# ArduinoRgbFanController.net
KiCad netlist of a schematic drawn in EAGLE
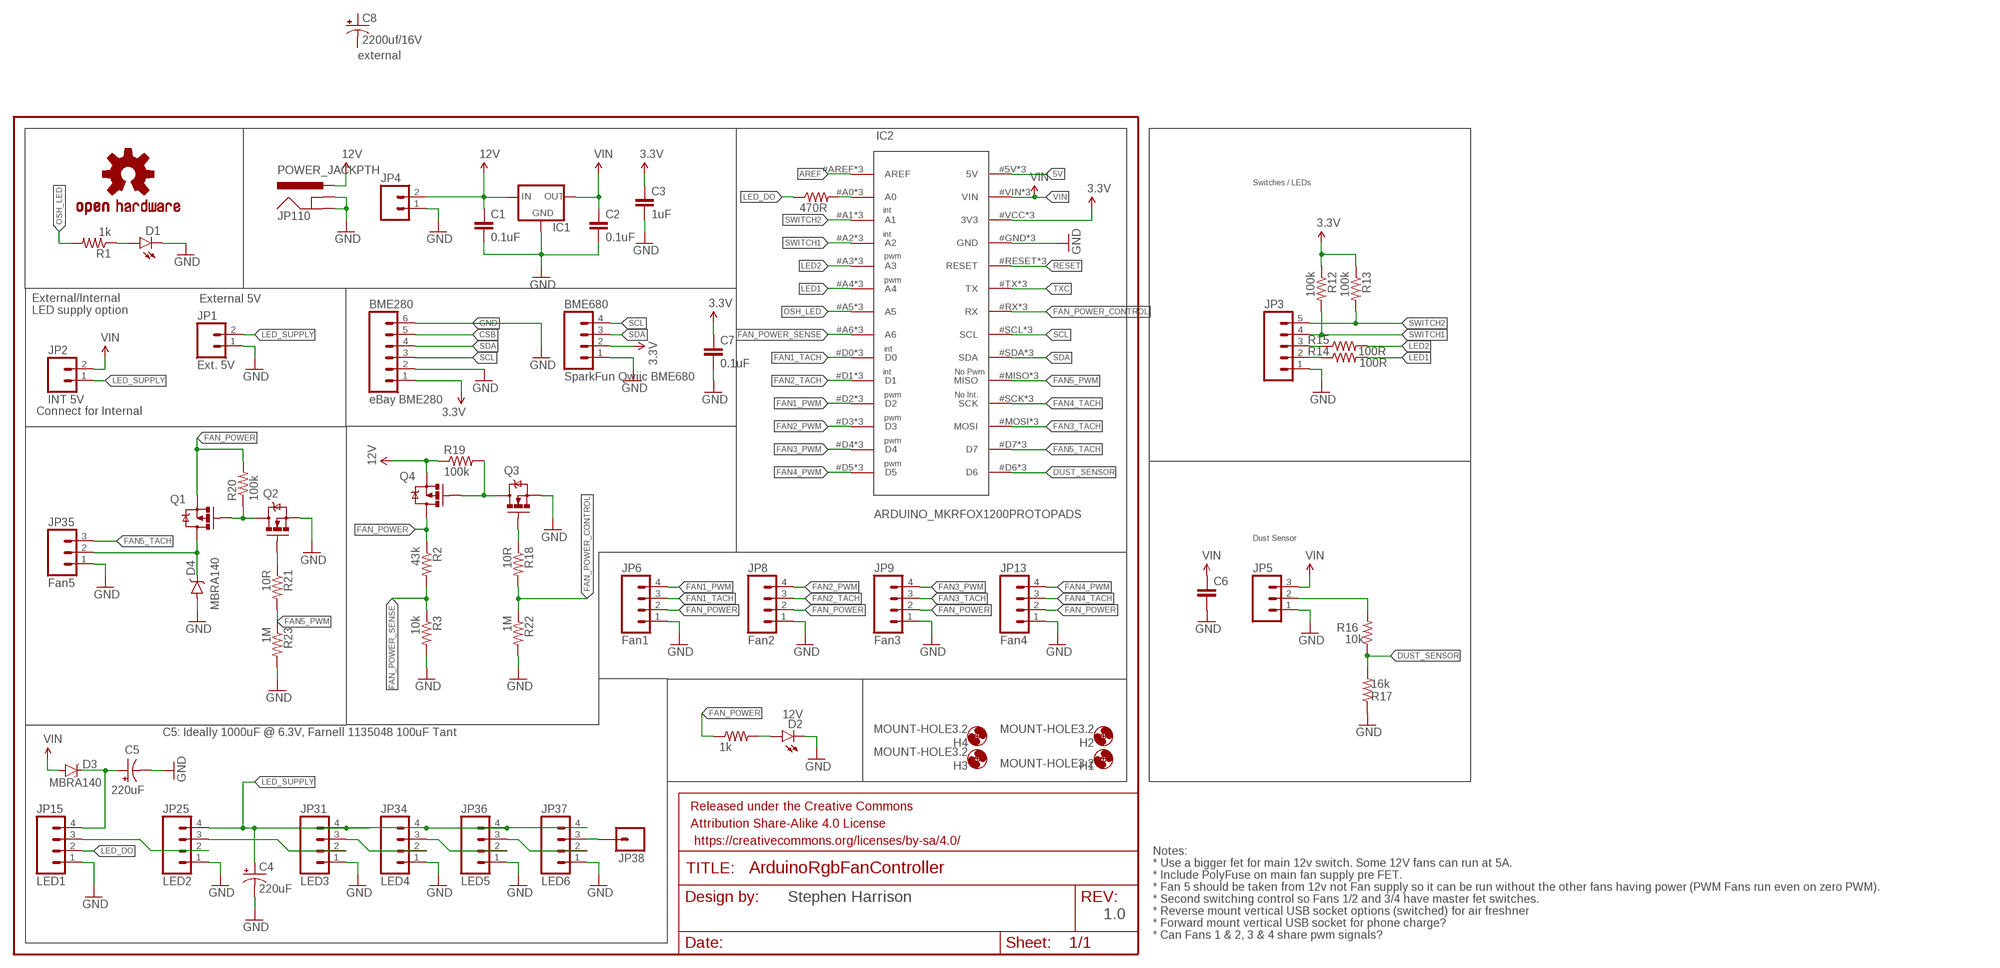
[diagram p0: schematic, sheet 1]

(export (version "E")
  (design (tool "Eeschema 10.0.6"))
  (components
    (comp (ref "BME280")
      (value "eBay BME280")
      (footprint "eagle-import:1X06")
      (libsource (lib "eagle-import") (part "M06SILK_FEMALE_PTH"))
    )
    (comp (ref "BME680")
      (value "SparkFun Qwiic BME680")
      (footprint "eagle-import:1X04")
      (libsource (lib "eagle-import") (part "M04PTH"))
    )
    (comp (ref "C1")
      (value "0.1uF")
      (footprint "eagle-import:0805-CAP")
      (libsource (lib "eagle-import") (part "1UF-25V-10%(0805){dblquote}"))
    )
    (comp (ref "C2")
      (value "0.1uF")
      (footprint "eagle-import:0805-CAP")
      (libsource (lib "eagle-import") (part "1UF-25V-10%(0805){dblquote}"))
    )
    (comp (ref "C3")
      (value "1uF")
      (footprint "eagle-import:0805-CAP")
      (libsource (lib "eagle-import") (part "1UF-25V-10%(0805){dblquote}"))
    )
    (comp (ref "C4")
      (value "220uF")
      (footprint "eagle-import:EIA3528")
      (libsource (lib "eagle-import") (part "47UF-10V-10%(TANT)"))
    )
    (comp (ref "C5")
      (value "220uF")
      (footprint "eagle-import:EIA3528")
      (libsource (lib "eagle-import") (part "47UF-10V-10%(TANT)"))
    )
    (comp (ref "C6")
      (value "1UF-25V-10%(0805)\"")
      (footprint "eagle-import:0805-CAP")
      (libsource (lib "eagle-import") (part "1UF-25V-10%(0805){dblquote}"))
    )
    (comp (ref "C7")
      (value "0.1uF")
      (footprint "eagle-import:0805-CAP")
      (libsource (lib "eagle-import") (part "1UF-25V-10%(0805){dblquote}"))
    )
    (comp (ref "C8")
      (value "2200uf/16V")
      (footprint "eagle-import:CPOL-RADIAL-1000UF-25V-KIT")
      (libsource (lib "eagle-import") (part "1000UF-25V(PTH)KIT"))
    )
    (comp (ref "D1")
      (value "LED1206-BOTTOM")
      (footprint "eagle-import:LED-1206-BOTTOM")
      (libsource (lib "eagle-import") (part "LED1206-BOTTOM"))
    )
    (comp (ref "D2")
      (value "12V")
      (footprint "eagle-import:LED-1206")
      (libsource (lib "eagle-import") (part "LED-RED1206"))
    )
    (comp (ref "D3")
      (value "MBRA140")
      (footprint "eagle-import:SMA-DIODE")
      (libsource (lib "eagle-import") (part "DIODE-SCHOTTKY-MBRA140"))
    )
    (comp (ref "D4")
      (value "MBRA140")
      (footprint "eagle-import:SMA-DIODE")
      (libsource (lib "eagle-import") (part "DIODE-SCHOTTKY-MBRA140"))
    )
    (comp (ref "FRAME1")
      (value "FRAME-LETTER")
      (footprint "eagle-import:CREATIVE_COMMONS")
      (libsource (lib "eagle-import") (part "FRAME-LETTER"))
    )
    (comp (ref "H1")
      (value "MOUNT-HOLE3.2")
      (footprint "eagle-import:3,2")
      (libsource (lib "eagle-import") (part "MOUNT-HOLE3.2"))
    )
    (comp (ref "H2")
      (value "MOUNT-HOLE3.2")
      (footprint "eagle-import:3,2")
      (libsource (lib "eagle-import") (part "MOUNT-HOLE3.2"))
    )
    (comp (ref "H3")
      (value "MOUNT-HOLE3.2")
      (footprint "eagle-import:3,2")
      (libsource (lib "eagle-import") (part "MOUNT-HOLE3.2"))
    )
    (comp (ref "H4")
      (value "MOUNT-HOLE3.2")
      (footprint "eagle-import:3,2")
      (libsource (lib "eagle-import") (part "MOUNT-HOLE3.2"))
    )
    (comp (ref "IC1")
      (value "78XXS")
      (footprint "eagle-import:78XXS")
      (libsource (lib "eagle-import") (part "78XXS"))
    )
    (comp (ref "IC2")
      (value "ARDUINO_MKRFOX1200PROTOPADS")
      (footprint "eagle-import:ARDUINO_MKRFOX1200_PROTOPADS")
      (libsource (lib "eagle-import") (part "ARDUINO_MKRFOX1200PROTOPADS"))
    )
    (comp (ref "JP1")
      (value "Ext. 5V")
      (footprint "eagle-import:SCREWTERMINAL-3.5MM-2")
      (libsource (lib "eagle-import") (part "M023.5MM"))
    )
    (comp (ref "JP2")
      (value "INT 5V")
      (footprint "eagle-import:1X02")
      (libsource (lib "eagle-import") (part "M02PTH"))
    )
    (comp (ref "JP3")
      (value "M05PTH")
      (footprint "eagle-import:1X05")
      (libsource (lib "eagle-import") (part "M05PTH"))
    )
    (comp (ref "JP4")
      (value "M025MM")
      (footprint "eagle-import:SCREWTERMINAL-5MM-2")
      (libsource (lib "eagle-import") (part "M025MM"))
    )
    (comp (ref "JP5")
      (value "M03POLAR")
      (footprint "eagle-import:MOLEX-1X3")
      (libsource (lib "eagle-import") (part "M03POLAR"))
    )
    (comp (ref "JP6")
      (value "Fan1")
      (footprint "eagle-import:MOLEX-1X4")
      (libsource (lib "eagle-import") (part "M04POLAR"))
    )
    (comp (ref "JP8")
      (value "Fan2")
      (footprint "eagle-import:MOLEX-1X4")
      (libsource (lib "eagle-import") (part "M04POLAR"))
    )
    (comp (ref "JP9")
      (value "Fan3")
      (footprint "eagle-import:MOLEX-1X4")
      (libsource (lib "eagle-import") (part "M04POLAR"))
    )
    (comp (ref "JP13")
      (value "Fan4")
      (footprint "eagle-import:MOLEX-1X4")
      (libsource (lib "eagle-import") (part "M04POLAR"))
    )
    (comp (ref "JP15")
      (value "LED1")
      (footprint "eagle-import:1X04")
      (libsource (lib "eagle-import") (part "M04PTH"))
    )
    (comp (ref "JP25")
      (value "LED2")
      (footprint "eagle-import:1X04")
      (libsource (lib "eagle-import") (part "M04PTH"))
    )
    (comp (ref "JP31")
      (value "LED3")
      (footprint "eagle-import:1X04")
      (libsource (lib "eagle-import") (part "M04PTH"))
    )
    (comp (ref "JP34")
      (value "LED4")
      (footprint "eagle-import:1X04")
      (libsource (lib "eagle-import") (part "M04PTH"))
    )
    (comp (ref "JP35")
      (value "Fan5")
      (footprint "eagle-import:MOLEX-1X3")
      (libsource (lib "eagle-import") (part "M03POLAR"))
    )
    (comp (ref "JP36")
      (value "LED5")
      (footprint "eagle-import:1X04")
      (libsource (lib "eagle-import") (part "M04PTH"))
    )
    (comp (ref "JP37")
      (value "LED6")
      (footprint "eagle-import:1X04")
      (libsource (lib "eagle-import") (part "M04PTH"))
    )
    (comp (ref "JP38")
      (value "M01PTH")
      (footprint "eagle-import:1X01")
      (libsource (lib "eagle-import") (part "M01PTH"))
    )
    (comp (ref "JP110")
      (value "POWER_JACKPTH")
      (footprint "eagle-import:POWER_JACK_PTH")
      (libsource (lib "eagle-import") (part "POWER_JACKPTH"))
    )
    (comp (ref "LOGO3")
      (value "OSHW-LOGOM")
      (footprint "eagle-import:OSHW-LOGO-M")
      (libsource (lib "eagle-import") (part "OSHW-LOGOM"))
    )
    (comp (ref "Q1")
      (value "IRLML930")
      (footprint "eagle-import:SOT23-3")
      (libsource (lib "eagle-import") (part "MOSFET-PCHANNEL"))
    )
    (comp (ref "Q2")
      (value "2N7002")
      (footprint "eagle-import:SOT23-3")
      (libsource (lib "eagle-import") (part "MOSFET-NCHANNELAO3404A"))
    )
    (comp (ref "Q3")
      (value "2N7002")
      (footprint "eagle-import:SOT23-3")
      (libsource (lib "eagle-import") (part "MOSFET-NCHANNELAO3404A"))
    )
    (comp (ref "Q4")
      (value "IRLML930")
      (footprint "eagle-import:SOT23-3")
      (libsource (lib "eagle-import") (part "MOSFET-PCHANNEL"))
    )
    (comp (ref "R1")
      (value "1k")
      (footprint "eagle-import:0805")
      (libsource (lib "eagle-import") (part "RESISTOR0805-RES"))
    )
    (comp (ref "R2")
      (value "43k")
      (footprint "eagle-import:0805")
      (libsource (lib "eagle-import") (part "RESISTOR0805-RES"))
    )
    (comp (ref "R3")
      (value "10k")
      (footprint "eagle-import:0805")
      (libsource (lib "eagle-import") (part "RESISTOR0805-RES"))
    )
    (comp (ref "R11")
      (value "470R")
      (footprint "eagle-import:0805")
      (libsource (lib "eagle-import") (part "RESISTOR0805-RES"))
    )
    (comp (ref "R12")
      (value "100k")
      (footprint "eagle-import:0805")
      (libsource (lib "eagle-import") (part "RESISTOR0805-RES"))
    )
    (comp (ref "R13")
      (value "100k")
      (footprint "eagle-import:0805")
      (libsource (lib "eagle-import") (part "RESISTOR0805-RES"))
    )
    (comp (ref "R14")
      (value "100R")
      (footprint "eagle-import:0805")
      (libsource (lib "eagle-import") (part "RESISTOR0805-RES"))
    )
    (comp (ref "R15")
      (value "100R")
      (footprint "eagle-import:0805")
      (libsource (lib "eagle-import") (part "RESISTOR0805-RES"))
    )
    (comp (ref "R16")
      (value "10k")
      (footprint "eagle-import:0805")
      (libsource (lib "eagle-import") (part "RESISTOR0805-RES"))
    )
    (comp (ref "R17")
      (value "16k")
      (footprint "eagle-import:0805")
      (libsource (lib "eagle-import") (part "RESISTOR0805-RES"))
    )
    (comp (ref "R18")
      (value "10R")
      (footprint "eagle-import:0805")
      (libsource (lib "eagle-import") (part "RESISTOR0805-RES"))
    )
    (comp (ref "R19")
      (value "100k")
      (footprint "eagle-import:0805")
      (libsource (lib "eagle-import") (part "RESISTOR0805-RES"))
    )
    (comp (ref "R20")
      (value "100k")
      (footprint "eagle-import:0805")
      (libsource (lib "eagle-import") (part "RESISTOR0805-RES"))
    )
    (comp (ref "R21")
      (value "10R")
      (footprint "eagle-import:0805")
      (libsource (lib "eagle-import") (part "RESISTOR0805-RES"))
    )
    (comp (ref "R22")
      (value "1M")
      (footprint "eagle-import:0805")
      (libsource (lib "eagle-import") (part "RESISTOR0805-RES"))
    )
    (comp (ref "R23")
      (value "1M")
      (footprint "eagle-import:0805")
      (libsource (lib "eagle-import") (part "RESISTOR0805-RES"))
    )
    (comp (ref "R28")
      (value "1k")
      (footprint "eagle-import:1206")
      (libsource (lib "eagle-import") (part "RESISTOR1206"))
    )
  )
  (nets
    (net (code "1") (name "3.3V") (class "Default")
      (node (ref "BME280") (pin "1") (pinfunction "1_1") (pintype "passive"))
      (node (ref "BME680") (pin "2") (pinfunction "2_2") (pintype "passive"))
      (node (ref "C3") (pin "1") (pinfunction "1_1") (pintype "passive"))
      (node (ref "C7") (pin "1") (pinfunction "1_1") (pintype "passive"))
      (node (ref "IC2") (pin "#VCC") (pinfunction "3V3_#VCC") (pintype "output"))
      (node (ref "IC2") (pin "@VCC") (pinfunction "3V3_@VCC") (pintype "output"))
      (node (ref "IC2") (pin "VCC") (pinfunction "3V3_VCC") (pintype "output"))
      (node (ref "R12") (pin "1") (pinfunction "1_1") (pintype "passive"))
      (node (ref "R13") (pin "1") (pinfunction "1_1") (pintype "passive"))
    )
    (net (code "2") (name "5V") (class "Default")
      (node (ref "IC2") (pin "#5V") (pinfunction "5V_#5V") (pintype "output"))
      (node (ref "IC2") (pin "5V") (pinfunction "5V_5V") (pintype "output"))
      (node (ref "IC2") (pin "@5V") (pinfunction "5V_@5V") (pintype "output"))
    )
    (net (code "3") (name "12V") (class "Default")
      (node (ref "C1") (pin "1") (pinfunction "1_1") (pintype "passive"))
      (node (ref "IC1") (pin "IN") (pinfunction "IN_IN") (pintype "input"))
      (node (ref "JP110") (pin "PWR") (pinfunction "PWR_PWR") (pintype "bidirectional"))
      (node (ref "JP4") (pin "2") (pinfunction "2_2") (pintype "passive"))
      (node (ref "Q4") (pin "2") (pinfunction "S_2") (pintype "passive"))
      (node (ref "R19") (pin "1") (pinfunction "1_1") (pintype "passive"))
    )
    (net (code "4") (name "AREF") (class "Default")
      (node (ref "IC2") (pin "#AREF") (pinfunction "AREF_#AREF") (pintype "bidirectional"))
      (node (ref "IC2") (pin "@AREF") (pinfunction "AREF_@AREF") (pintype "bidirectional"))
      (node (ref "IC2") (pin "AREF") (pinfunction "AREF_AREF") (pintype "bidirectional"))
    )
    (net (code "5") (name "CSB") (class "Default")
      (node (ref "BME280") (pin "5") (pinfunction "5_5") (pintype "passive"))
    )
    (net (code "6") (name "DUST_SENSOR") (class "Default")
      (node (ref "IC2") (pin "#D6") (pinfunction "D6_#D6") (pintype "bidirectional"))
      (node (ref "IC2") (pin "@D6") (pinfunction "D6_@D6") (pintype "bidirectional"))
      (node (ref "IC2") (pin "D6") (pinfunction "D6_D6") (pintype "bidirectional"))
      (node (ref "R16") (pin "1") (pinfunction "1_1") (pintype "passive"))
      (node (ref "R17") (pin "2") (pinfunction "2_2") (pintype "passive"))
    )
    (net (code "7") (name "FAN1_PWM") (class "Default")
      (node (ref "IC2") (pin "#D2") (pinfunction "D2_#D2") (pintype "bidirectional"))
      (node (ref "IC2") (pin "@D2") (pinfunction "D2_@D2") (pintype "bidirectional"))
      (node (ref "IC2") (pin "D2") (pinfunction "D2_D2") (pintype "bidirectional"))
      (node (ref "JP6") (pin "4") (pinfunction "4_4") (pintype "passive"))
    )
    (net (code "8") (name "FAN1_TACH") (class "Default")
      (node (ref "IC2") (pin "#D0") (pinfunction "D0_#D0") (pintype "bidirectional"))
      (node (ref "IC2") (pin "@D0") (pinfunction "D0_@D0") (pintype "bidirectional"))
      (node (ref "IC2") (pin "D0") (pinfunction "D0_D0") (pintype "bidirectional"))
      (node (ref "JP6") (pin "3") (pinfunction "3_3") (pintype "passive"))
    )
    (net (code "9") (name "FAN2_PWM") (class "Default")
      (node (ref "IC2") (pin "#D3") (pinfunction "D3_#D3") (pintype "bidirectional"))
      (node (ref "IC2") (pin "@D3") (pinfunction "D3_@D3") (pintype "bidirectional"))
      (node (ref "IC2") (pin "D3") (pinfunction "D3_D3") (pintype "bidirectional"))
      (node (ref "JP8") (pin "4") (pinfunction "4_4") (pintype "passive"))
    )
    (net (code "10") (name "FAN2_TACH") (class "Default")
      (node (ref "IC2") (pin "#D1") (pinfunction "D1_#D1") (pintype "bidirectional"))
      (node (ref "IC2") (pin "@D1") (pinfunction "D1_@D1") (pintype "bidirectional"))
      (node (ref "IC2") (pin "D1") (pinfunction "D1_D1") (pintype "bidirectional"))
      (node (ref "JP8") (pin "3") (pinfunction "3_3") (pintype "passive"))
    )
    (net (code "11") (name "FAN3_PWM") (class "Default")
      (node (ref "IC2") (pin "#D4") (pinfunction "D4_#D4") (pintype "bidirectional"))
      (node (ref "IC2") (pin "@D4") (pinfunction "D4_@D4") (pintype "bidirectional"))
      (node (ref "IC2") (pin "D4") (pinfunction "D4_D4") (pintype "bidirectional"))
      (node (ref "JP9") (pin "4") (pinfunction "4_4") (pintype "passive"))
    )
    (net (code "12") (name "FAN3_TACH") (class "Default")
      (node (ref "IC2") (pin "#MOSI") (pinfunction "MOSI_#MOSI") (pintype "bidirectional"))
      (node (ref "IC2") (pin "@MOSI") (pinfunction "MOSI_@MOSI") (pintype "bidirectional"))
      (node (ref "IC2") (pin "MOSI") (pinfunction "MOSI_MOSI") (pintype "bidirectional"))
      (node (ref "JP9") (pin "3") (pinfunction "3_3") (pintype "passive"))
    )
    (net (code "13") (name "FAN4_PWM") (class "Default")
      (node (ref "IC2") (pin "#D5") (pinfunction "D5_#D5") (pintype "bidirectional"))
      (node (ref "IC2") (pin "@D5") (pinfunction "D5_@D5") (pintype "bidirectional"))
      (node (ref "IC2") (pin "D5") (pinfunction "D5_D5") (pintype "bidirectional"))
      (node (ref "JP13") (pin "4") (pinfunction "4_4") (pintype "passive"))
    )
    (net (code "14") (name "FAN4_TACH") (class "Default")
      (node (ref "IC2") (pin "#SCK") (pinfunction "SCK_#SCK") (pintype "bidirectional"))
      (node (ref "IC2") (pin "@SCK") (pinfunction "SCK_@SCK") (pintype "bidirectional"))
      (node (ref "IC2") (pin "SCK") (pinfunction "SCK_SCK") (pintype "bidirectional"))
      (node (ref "JP13") (pin "3") (pinfunction "3_3") (pintype "passive"))
    )
    (net (code "15") (name "FAN5_PWM") (class "Default")
      (node (ref "IC2") (pin "#MISO") (pinfunction "MISO_#MISO") (pintype "bidirectional"))
      (node (ref "IC2") (pin "@MISO") (pinfunction "MISO_@MISO") (pintype "bidirectional"))
      (node (ref "IC2") (pin "MISO") (pinfunction "MISO_MISO") (pintype "bidirectional"))
      (node (ref "R21") (pin "2") (pinfunction "2_2") (pintype "passive"))
      (node (ref "R23") (pin "1") (pinfunction "1_1") (pintype "passive"))
    )
    (net (code "16") (name "FAN5_TACH") (class "Default")
      (node (ref "IC2") (pin "#D7") (pinfunction "D7_#D7") (pintype "bidirectional"))
      (node (ref "IC2") (pin "@D7") (pinfunction "D7_@D7") (pintype "bidirectional"))
      (node (ref "IC2") (pin "D7") (pinfunction "D7_D7") (pintype "bidirectional"))
      (node (ref "JP35") (pin "3") (pinfunction "3_3") (pintype "passive"))
    )
    (net (code "17") (name "FAN_POWER") (class "Default")
      (node (ref "JP13") (pin "2") (pinfunction "2_2") (pintype "passive"))
      (node (ref "JP6") (pin "2") (pinfunction "2_2") (pintype "passive"))
      (node (ref "JP8") (pin "2") (pinfunction "2_2") (pintype "passive"))
      (node (ref "JP9") (pin "2") (pinfunction "2_2") (pintype "passive"))
      (node (ref "Q1") (pin "2") (pinfunction "S_2") (pintype "passive"))
      (node (ref "Q4") (pin "3") (pinfunction "D_3") (pintype "passive"))
      (node (ref "R2") (pin "1") (pinfunction "1_1") (pintype "passive"))
      (node (ref "R20") (pin "2") (pinfunction "2_2") (pintype "passive"))
      (node (ref "R28") (pin "1") (pinfunction "1_1") (pintype "passive"))
    )
    (net (code "18") (name "FAN_POWER_CONTROL") (class "Default")
      (node (ref "IC2") (pin "#RX") (pinfunction "RX_#RX") (pintype "bidirectional"))
      (node (ref "IC2") (pin "@RX") (pinfunction "RX_@RX") (pintype "bidirectional"))
      (node (ref "IC2") (pin "RX") (pinfunction "RX_RX") (pintype "bidirectional"))
      (node (ref "R18") (pin "2") (pinfunction "2_2") (pintype "passive"))
      (node (ref "R22") (pin "1") (pinfunction "1_1") (pintype "passive"))
    )
    (net (code "19") (name "FAN_POWER_SENSE") (class "Default")
      (node (ref "IC2") (pin "#A6") (pinfunction "A6_#A6") (pintype "bidirectional"))
      (node (ref "IC2") (pin "@A6") (pinfunction "A6_@A6") (pintype "bidirectional"))
      (node (ref "IC2") (pin "A6") (pinfunction "A6_A6") (pintype "bidirectional"))
      (node (ref "R2") (pin "2") (pinfunction "2_2") (pintype "passive"))
      (node (ref "R3") (pin "1") (pinfunction "1_1") (pintype "passive"))
    )
    (net (code "20") (name "GND") (class "Default")
      (node (ref "BME280") (pin "2") (pinfunction "2_2") (pintype "passive"))
      (node (ref "BME280") (pin "6") (pinfunction "6_6") (pintype "passive"))
      (node (ref "BME680") (pin "1") (pinfunction "1_1") (pintype "passive"))
      (node (ref "C1") (pin "2") (pinfunction "2_2") (pintype "passive"))
      (node (ref "C2") (pin "2") (pinfunction "2_2") (pintype "passive"))
      (node (ref "C3") (pin "2") (pinfunction "2_2") (pintype "passive"))
      (node (ref "C4") (pin "C") (pinfunction "-_C") (pintype "passive"))
      (node (ref "C5") (pin "C") (pinfunction "-_C") (pintype "passive"))
      (node (ref "C6") (pin "2") (pinfunction "2_2") (pintype "passive"))
      (node (ref "C7") (pin "2") (pinfunction "2_2") (pintype "passive"))
      (node (ref "D1") (pin "C") (pinfunction "C_C") (pintype "passive"))
      (node (ref "D2") (pin "C") (pinfunction "C_C") (pintype "passive"))
      (node (ref "D4") (pin "A") (pinfunction "A_A") (pintype "passive"))
      (node (ref "IC1") (pin "GND") (pinfunction "GND_GND") (pintype "input"))
      (node (ref "IC2") (pin "#GND") (pinfunction "GND_#GND") (pintype "power_in"))
      (node (ref "IC2") (pin "@GND") (pinfunction "GND_@GND") (pintype "power_in"))
      (node (ref "IC2") (pin "GND") (pinfunction "GND_GND") (pintype "power_in"))
      (node (ref "JP1") (pin "1") (pinfunction "1_1") (pintype "passive"))
      (node (ref "JP110") (pin "GND") (pinfunction "GND_GND") (pintype "bidirectional"))
      (node (ref "JP110") (pin "GNDBREAK") (pinfunction "GNDBREAK_GNDBREAK") (pintype "bidirectional"))
      (node (ref "JP13") (pin "1") (pinfunction "1_1") (pintype "passive"))
      (node (ref "JP15") (pin "1") (pinfunction "1_1") (pintype "passive"))
      (node (ref "JP25") (pin "1") (pinfunction "1_1") (pintype "passive"))
      (node (ref "JP3") (pin "1") (pinfunction "1_1") (pintype "passive"))
      (node (ref "JP31") (pin "1") (pinfunction "1_1") (pintype "passive"))
      (node (ref "JP34") (pin "1") (pinfunction "1_1") (pintype "passive"))
      (node (ref "JP35") (pin "1") (pinfunction "1_1") (pintype "passive"))
      (node (ref "JP36") (pin "1") (pinfunction "1_1") (pintype "passive"))
      (node (ref "JP37") (pin "1") (pinfunction "1_1") (pintype "passive"))
      (node (ref "JP4") (pin "1") (pinfunction "1_1") (pintype "passive"))
      (node (ref "JP5") (pin "1") (pinfunction "1_1") (pintype "passive"))
      (node (ref "JP6") (pin "1") (pinfunction "1_1") (pintype "passive"))
      (node (ref "JP8") (pin "1") (pinfunction "1_1") (pintype "passive"))
      (node (ref "JP9") (pin "1") (pinfunction "1_1") (pintype "passive"))
      (node (ref "Q2") (pin "2") (pinfunction "S_2") (pintype "passive"))
      (node (ref "Q3") (pin "2") (pinfunction "S_2") (pintype "passive"))
      (node (ref "R17") (pin "1") (pinfunction "1_1") (pintype "passive"))
      (node (ref "R22") (pin "2") (pinfunction "2_2") (pintype "passive"))
      (node (ref "R23") (pin "2") (pinfunction "2_2") (pintype "passive"))
      (node (ref "R3") (pin "2") (pinfunction "2_2") (pintype "passive"))
    )
    (net (code "21") (name "LED1") (class "Default")
      (node (ref "IC2") (pin "#A4") (pinfunction "A4_#A4") (pintype "bidirectional"))
      (node (ref "IC2") (pin "@A4") (pinfunction "A4_@A4") (pintype "bidirectional"))
      (node (ref "IC2") (pin "A4") (pinfunction "A4_A4") (pintype "bidirectional"))
      (node (ref "R14") (pin "2") (pinfunction "2_2") (pintype "passive"))
    )
    (net (code "22") (name "LED2") (class "Default")
      (node (ref "IC2") (pin "#A3") (pinfunction "A3_#A3") (pintype "bidirectional"))
      (node (ref "IC2") (pin "@A3") (pinfunction "A3_@A3") (pintype "bidirectional"))
      (node (ref "IC2") (pin "A3") (pinfunction "A3_A3") (pintype "bidirectional"))
      (node (ref "R15") (pin "2") (pinfunction "2_2") (pintype "passive"))
    )
    (net (code "23") (name "LED_DO") (class "Default")
      (node (ref "JP15") (pin "2") (pinfunction "2_2") (pintype "passive"))
      (node (ref "R11") (pin "1") (pinfunction "1_1") (pintype "passive"))
    )
    (net (code "24") (name "LED_SUPPLY") (class "Default")
      (node (ref "C4") (pin "A") (pinfunction "+_A") (pintype "passive"))
      (node (ref "JP1") (pin "2") (pinfunction "2_2") (pintype "passive"))
      (node (ref "JP2") (pin "1") (pinfunction "1_1") (pintype "passive"))
      (node (ref "JP25") (pin "4") (pinfunction "4_4") (pintype "passive"))
      (node (ref "JP31") (pin "4") (pinfunction "4_4") (pintype "passive"))
      (node (ref "JP34") (pin "4") (pinfunction "4_4") (pintype "passive"))
      (node (ref "JP36") (pin "4") (pinfunction "4_4") (pintype "passive"))
      (node (ref "JP37") (pin "4") (pinfunction "4_4") (pintype "passive"))
    )
    (net (code "25") (name "Net-(C5-+)") (class "Default")
      (node (ref "C5") (pin "A") (pinfunction "+_A") (pintype "passive"))
      (node (ref "D3") (pin "C") (pinfunction "C_C") (pintype "passive"))
      (node (ref "JP15") (pin "4") (pinfunction "4_4") (pintype "passive"))
    )
    (net (code "26") (name "Net-(D1-PadA)") (class "Default")
      (node (ref "D1") (pin "A") (pinfunction "A_A") (pintype "passive"))
      (node (ref "R1") (pin "1") (pinfunction "1_1") (pintype "passive"))
    )
    (net (code "27") (name "Net-(D2-PadA)") (class "Default")
      (node (ref "D2") (pin "A") (pinfunction "A_A") (pintype "passive"))
      (node (ref "R28") (pin "2") (pinfunction "2_2") (pintype "passive"))
    )
    (net (code "28") (name "Net-(IC2-A0-Pad#A0)") (class "Default")
      (node (ref "IC2") (pin "#A0") (pinfunction "A0_#A0") (pintype "bidirectional"))
      (node (ref "IC2") (pin "@A0") (pinfunction "A0_@A0") (pintype "bidirectional"))
      (node (ref "IC2") (pin "A0") (pinfunction "A0_A0") (pintype "bidirectional"))
      (node (ref "R11") (pin "2") (pinfunction "2_2") (pintype "passive"))
    )
    (net (code "29") (name "Net-(JP3-Pad2)") (class "Default")
      (node (ref "JP3") (pin "2") (pinfunction "2_2") (pintype "passive"))
      (node (ref "R14") (pin "1") (pinfunction "1_1") (pintype "passive"))
    )
    (net (code "30") (name "Net-(JP3-Pad3)") (class "Default")
      (node (ref "JP3") (pin "3") (pinfunction "3_3") (pintype "passive"))
      (node (ref "R15") (pin "1") (pinfunction "1_1") (pintype "passive"))
    )
    (net (code "31") (name "Net-(JP5-Pad2)") (class "Default")
      (node (ref "JP5") (pin "2") (pinfunction "2_2") (pintype "passive"))
      (node (ref "R16") (pin "2") (pinfunction "2_2") (pintype "passive"))
    )
    (net (code "32") (name "Net-(JP15-Pad3)") (class "Default")
      (node (ref "JP15") (pin "3") (pinfunction "3_3") (pintype "passive"))
      (node (ref "JP25") (pin "2") (pinfunction "2_2") (pintype "passive"))
    )
    (net (code "33") (name "Net-(JP25-Pad3)") (class "Default")
      (node (ref "JP25") (pin "3") (pinfunction "3_3") (pintype "passive"))
      (node (ref "JP31") (pin "2") (pinfunction "2_2") (pintype "passive"))
    )
    (net (code "34") (name "Net-(JP31-Pad3)") (class "Default")
      (node (ref "JP31") (pin "3") (pinfunction "3_3") (pintype "passive"))
      (node (ref "JP34") (pin "2") (pinfunction "2_2") (pintype "passive"))
    )
    (net (code "35") (name "Net-(JP34-Pad3)") (class "Default")
      (node (ref "JP34") (pin "3") (pinfunction "3_3") (pintype "passive"))
      (node (ref "JP36") (pin "2") (pinfunction "2_2") (pintype "passive"))
    )
    (net (code "36") (name "Net-(JP36-Pad3)") (class "Default")
      (node (ref "JP36") (pin "3") (pinfunction "3_3") (pintype "passive"))
      (node (ref "JP37") (pin "2") (pinfunction "2_2") (pintype "passive"))
    )
    (net (code "37") (name "Net-(JP37-Pad3)") (class "Default")
      (node (ref "JP37") (pin "3") (pinfunction "3_3") (pintype "passive"))
      (node (ref "JP38") (pin "1") (pinfunction "1_1") (pintype "passive"))
    )
    (net (code "38") (name "Net-(Q1-D)") (class "Default")
      (node (ref "D4") (pin "C") (pinfunction "C_C") (pintype "passive"))
      (node (ref "JP35") (pin "2") (pinfunction "2_2") (pintype "passive"))
      (node (ref "Q1") (pin "3") (pinfunction "D_3") (pintype "passive"))
    )
    (net (code "39") (name "Net-(Q1-G)") (class "Default")
      (node (ref "Q1") (pin "1") (pinfunction "G_1") (pintype "passive"))
      (node (ref "Q2") (pin "3") (pinfunction "D_3") (pintype "passive"))
      (node (ref "R20") (pin "1") (pinfunction "1_1") (pintype "passive"))
    )
    (net (code "40") (name "Net-(Q2-G)") (class "Default")
      (node (ref "Q2") (pin "1") (pinfunction "G_1") (pintype "passive"))
      (node (ref "R21") (pin "1") (pinfunction "1_1") (pintype "passive"))
    )
    (net (code "41") (name "Net-(Q3-D)") (class "Default")
      (node (ref "Q3") (pin "3") (pinfunction "D_3") (pintype "passive"))
      (node (ref "Q4") (pin "1") (pinfunction "G_1") (pintype "passive"))
      (node (ref "R19") (pin "2") (pinfunction "2_2") (pintype "passive"))
    )
    (net (code "42") (name "Net-(Q3-G)") (class "Default")
      (node (ref "Q3") (pin "1") (pinfunction "G_1") (pintype "passive"))
      (node (ref "R18") (pin "1") (pinfunction "1_1") (pintype "passive"))
    )
    (net (code "43") (name "OSH_LED") (class "Default")
      (node (ref "IC2") (pin "#A5") (pinfunction "A5_#A5") (pintype "bidirectional"))
      (node (ref "IC2") (pin "@A5") (pinfunction "A5_@A5") (pintype "bidirectional"))
      (node (ref "IC2") (pin "A5") (pinfunction "A5_A5") (pintype "bidirectional"))
      (node (ref "R1") (pin "2") (pinfunction "2_2") (pintype "passive"))
    )
    (net (code "44") (name "RESET") (class "Default")
      (node (ref "IC2") (pin "#RESET") (pinfunction "RESET_#RESET") (pintype "bidirectional"))
      (node (ref "IC2") (pin "@RESET") (pinfunction "RESET_@RESET") (pintype "bidirectional"))
      (node (ref "IC2") (pin "RESET") (pinfunction "RESET_RESET") (pintype "bidirectional"))
    )
    (net (code "45") (name "SCL") (class "Default")
      (node (ref "BME280") (pin "3") (pinfunction "3_3") (pintype "passive"))
      (node (ref "BME680") (pin "4") (pinfunction "4_4") (pintype "passive"))
      (node (ref "IC2") (pin "#SCL") (pinfunction "SCL_#SCL") (pintype "bidirectional"))
      (node (ref "IC2") (pin "@SCL") (pinfunction "SCL_@SCL") (pintype "bidirectional"))
      (node (ref "IC2") (pin "SCL") (pinfunction "SCL_SCL") (pintype "bidirectional"))
    )
    (net (code "46") (name "SDA") (class "Default")
      (node (ref "BME280") (pin "4") (pinfunction "4_4") (pintype "passive"))
      (node (ref "BME680") (pin "3") (pinfunction "3_3") (pintype "passive"))
      (node (ref "IC2") (pin "#SDA") (pinfunction "SDA_#SDA") (pintype "bidirectional"))
      (node (ref "IC2") (pin "@SDA") (pinfunction "SDA_@SDA") (pintype "bidirectional"))
      (node (ref "IC2") (pin "SDA") (pinfunction "SDA_SDA") (pintype "bidirectional"))
    )
    (net (code "47") (name "SWITCH1") (class "Default")
      (node (ref "IC2") (pin "#A2") (pinfunction "A2_#A2") (pintype "bidirectional"))
      (node (ref "IC2") (pin "@A2") (pinfunction "A2_@A2") (pintype "bidirectional"))
      (node (ref "IC2") (pin "A2") (pinfunction "A2_A2") (pintype "bidirectional"))
      (node (ref "JP3") (pin "4") (pinfunction "4_4") (pintype "passive"))
      (node (ref "R12") (pin "2") (pinfunction "2_2") (pintype "passive"))
    )
    (net (code "48") (name "SWITCH2") (class "Default")
      (node (ref "IC2") (pin "#A1") (pinfunction "A1_#A1") (pintype "bidirectional"))
      (node (ref "IC2") (pin "@A1") (pinfunction "A1_@A1") (pintype "bidirectional"))
      (node (ref "IC2") (pin "A1") (pinfunction "A1_A1") (pintype "bidirectional"))
      (node (ref "JP3") (pin "5") (pinfunction "5_5") (pintype "passive"))
      (node (ref "R13") (pin "2") (pinfunction "2_2") (pintype "passive"))
    )
    (net (code "49") (name "TXC") (class "Default")
      (node (ref "IC2") (pin "#TX") (pinfunction "TX_#TX") (pintype "bidirectional"))
      (node (ref "IC2") (pin "@TX") (pinfunction "TX_@TX") (pintype "bidirectional"))
      (node (ref "IC2") (pin "TX") (pinfunction "TX_TX") (pintype "bidirectional"))
    )
    (net (code "50") (name "VIN") (class "Default")
      (node (ref "C2") (pin "1") (pinfunction "1_1") (pintype "passive"))
      (node (ref "C6") (pin "1") (pinfunction "1_1") (pintype "passive"))
      (node (ref "D3") (pin "A") (pinfunction "A_A") (pintype "passive"))
      (node (ref "IC1") (pin "OUT") (pinfunction "OUT_OUT") (pintype "passive"))
      (node (ref "IC2") (pin "#VIN") (pinfunction "VIN_#VIN") (pintype "input"))
      (node (ref "IC2") (pin "@VIN") (pinfunction "VIN_@VIN") (pintype "input"))
      (node (ref "IC2") (pin "VIN") (pinfunction "VIN_VIN") (pintype "input"))
      (node (ref "JP2") (pin "2") (pinfunction "2_2") (pintype "passive"))
      (node (ref "JP5") (pin "3") (pinfunction "3_3") (pintype "passive"))
    )
    (net (code "51") (name "unconnected-(C8-Pad+)") (class "Default")
      (node (ref "C8") (pin "+") (pinfunction "+_+") (pintype "passive"))
    )
    (net (code "52") (name "unconnected-(C8-Pad-)") (class "Default")
      (node (ref "C8") (pin "-") (pinfunction "-_-") (pintype "passive"))
    )
  )
)
